# SCH_SD_CARD_2024-02-26.net
KiCad netlist of a schematic drawn in EasyEDA
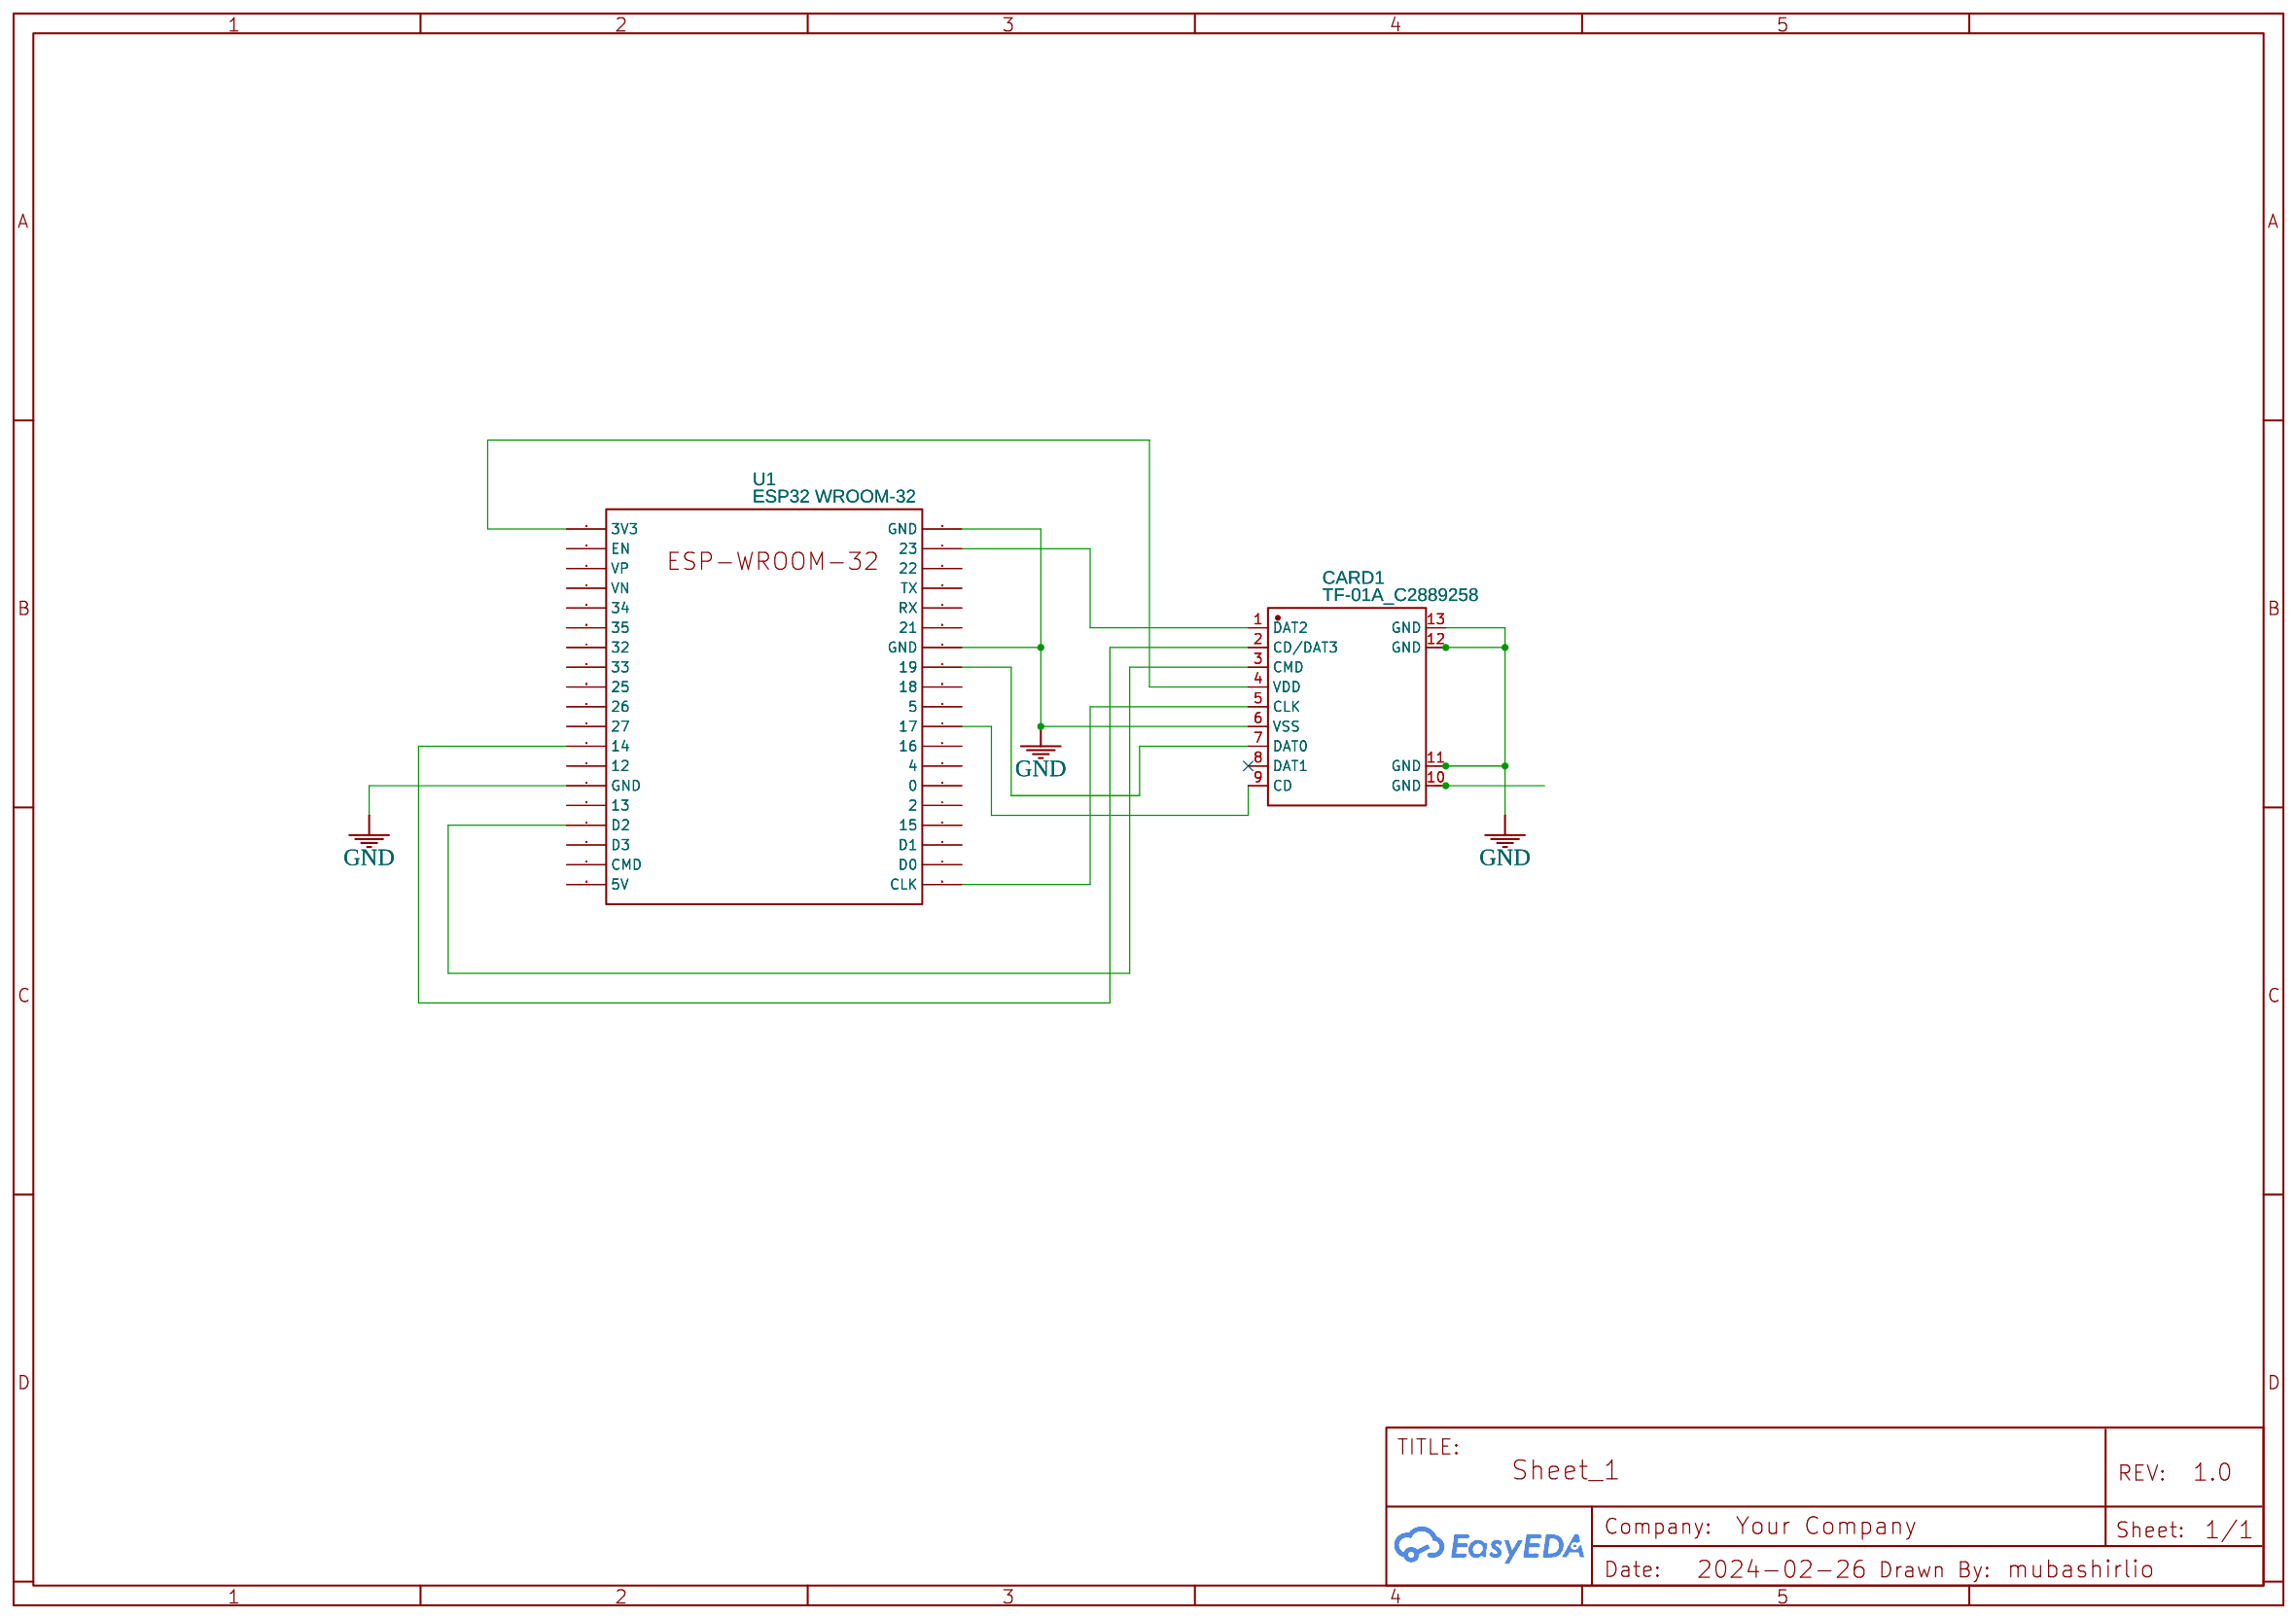
[diagram p0: schematic sheet]

(export (version "E")
  (design (tool "Eeschema 10.0.6"))
  (components
    (comp (ref "CARD1")
      (value "TF-01A_C2889258")
      (fields (field (name "Manufacturer Part") "TF-01A") (field (name "Manufacturer") "Yuandi(台湾元迪)"))
      (libsource (lib "") (part "TF-01A_C2889258"))
    )
    (comp (ref "U1") (value "ESP32 WROOM-32") (libsource (lib "") (part "ESP32 WROOM-32")))
  )
  (nets
    (net (code "1") (name "GND") (class "Default")
      (node (ref "CARD1") (pin "11") (pinfunction "GND_11") (pintype "unspecified"))
      (node (ref "CARD1") (pin "12") (pinfunction "GND_12") (pintype "unspecified"))
      (node (ref "CARD1") (pin "13") (pinfunction "GND_13") (pintype "unspecified"))
      (node (ref "CARD1") (pin "6") (pinfunction "VSS_6") (pintype "unspecified"))
      (node (ref "U1") (pin "14") (pinfunction "GND_14") (pintype "unspecified"))
      (node (ref "U1") (pin "32") (pinfunction "GND_32") (pintype "unspecified"))
      (node (ref "U1") (pin "38") (pinfunction "GND_38") (pintype "unspecified"))
    )
    (net (code "2") (name "Net-(CARD1-CD)") (class "Default")
      (node (ref "CARD1") (pin "9") (pinfunction "CD_9") (pintype "unspecified"))
      (node (ref "U1") (pin "28") (pinfunction "17_28") (pintype "unspecified"))
    )
    (net (code "3") (name "Net-(CARD1-CD{slash}DAT3)") (class "Default")
      (node (ref "CARD1") (pin "2") (pinfunction "CD/DAT3_2") (pintype "unspecified"))
      (node (ref "U1") (pin "12") (pinfunction "14_12") (pintype "unspecified"))
    )
    (net (code "4") (name "Net-(CARD1-CLK)") (class "Default")
      (node (ref "CARD1") (pin "5") (pinfunction "CLK_5") (pintype "unspecified"))
      (node (ref "U1") (pin "20") (pinfunction "CLK_20") (pintype "unspecified"))
    )
    (net (code "5") (name "Net-(CARD1-CMD)") (class "Default")
      (node (ref "CARD1") (pin "3") (pinfunction "CMD_3") (pintype "unspecified"))
      (node (ref "U1") (pin "16") (pinfunction "D2_16") (pintype "unspecified"))
    )
    (net (code "6") (name "Net-(CARD1-DAT0)") (class "Default")
      (node (ref "CARD1") (pin "7") (pinfunction "DAT0_7") (pintype "unspecified"))
      (node (ref "U1") (pin "31") (pinfunction "19_31") (pintype "unspecified"))
    )
    (net (code "7") (name "Net-(CARD1-DAT2)") (class "Default")
      (node (ref "CARD1") (pin "1") (pinfunction "DAT2_1") (pintype "unspecified"))
      (node (ref "U1") (pin "37") (pinfunction "23_37") (pintype "unspecified"))
    )
    (net (code "8") (name "Net-(CARD1-VDD)") (class "Default")
      (node (ref "CARD1") (pin "4") (pinfunction "VDD_4") (pintype "unspecified"))
      (node (ref "U1") (pin "1") (pinfunction "3V3_1") (pintype "unspecified"))
    )
    (net (code "9") (name "unconnected-(CARD1-DAT1-Pad8)") (class "Default")
      (node (ref "CARD1") (pin "8") (pinfunction "DAT1_8") (pintype "unspecified+no_connect"))
    )
    (net (code "10") (name "unconnected-(CARD1-GND-Pad10)") (class "Default")
      (node (ref "CARD1") (pin "10") (pinfunction "GND_10") (pintype "unspecified"))
    )
    (net (code "11") (name "unconnected-(U1-0-Pad25)") (class "Default")
      (node (ref "U1") (pin "25") (pinfunction "0_25") (pintype "unspecified"))
    )
    (net (code "12") (name "unconnected-(U1-2-Pad24)") (class "Default")
      (node (ref "U1") (pin "24") (pinfunction "2_24") (pintype "unspecified"))
    )
    (net (code "13") (name "unconnected-(U1-4-Pad26)") (class "Default")
      (node (ref "U1") (pin "26") (pinfunction "4_26") (pintype "unspecified"))
    )
    (net (code "14") (name "unconnected-(U1-5-Pad29)") (class "Default")
      (node (ref "U1") (pin "29") (pinfunction "5_29") (pintype "unspecified"))
    )
    (net (code "15") (name "unconnected-(U1-5V-Pad19)") (class "Default")
      (node (ref "U1") (pin "19") (pinfunction "5V_19") (pintype "unspecified"))
    )
    (net (code "16") (name "unconnected-(U1-12-Pad13)") (class "Default")
      (node (ref "U1") (pin "13") (pinfunction "12_13") (pintype "unspecified"))
    )
    (net (code "17") (name "unconnected-(U1-13-Pad15)") (class "Default")
      (node (ref "U1") (pin "15") (pinfunction "13_15") (pintype "unspecified"))
    )
    (net (code "18") (name "unconnected-(U1-15-Pad23)") (class "Default")
      (node (ref "U1") (pin "23") (pinfunction "15_23") (pintype "unspecified"))
    )
    (net (code "19") (name "unconnected-(U1-16-Pad27)") (class "Default")
      (node (ref "U1") (pin "27") (pinfunction "16_27") (pintype "unspecified"))
    )
    (net (code "20") (name "unconnected-(U1-18-Pad30)") (class "Default")
      (node (ref "U1") (pin "30") (pinfunction "18_30") (pintype "unspecified"))
    )
    (net (code "21") (name "unconnected-(U1-21-Pad33)") (class "Default")
      (node (ref "U1") (pin "33") (pinfunction "21_33") (pintype "unspecified"))
    )
    (net (code "22") (name "unconnected-(U1-22-Pad36)") (class "Default")
      (node (ref "U1") (pin "36") (pinfunction "22_36") (pintype "unspecified"))
    )
    (net (code "23") (name "unconnected-(U1-25-Pad9)") (class "Default")
      (node (ref "U1") (pin "9") (pinfunction "25_9") (pintype "unspecified"))
    )
    (net (code "24") (name "unconnected-(U1-26-Pad10)") (class "Default")
      (node (ref "U1") (pin "10") (pinfunction "26_10") (pintype "unspecified"))
    )
    (net (code "25") (name "unconnected-(U1-27-Pad11)") (class "Default")
      (node (ref "U1") (pin "11") (pinfunction "27_11") (pintype "unspecified"))
    )
    (net (code "26") (name "unconnected-(U1-32-Pad7)") (class "Default")
      (node (ref "U1") (pin "7") (pinfunction "32_7") (pintype "unspecified"))
    )
    (net (code "27") (name "unconnected-(U1-33-Pad8)") (class "Default")
      (node (ref "U1") (pin "8") (pinfunction "33_8") (pintype "unspecified"))
    )
    (net (code "28") (name "unconnected-(U1-34-Pad5)") (class "Default")
      (node (ref "U1") (pin "5") (pinfunction "34_5") (pintype "unspecified"))
    )
    (net (code "29") (name "unconnected-(U1-35-Pad6)") (class "Default")
      (node (ref "U1") (pin "6") (pinfunction "35_6") (pintype "unspecified"))
    )
    (net (code "30") (name "unconnected-(U1-CMD-Pad18)") (class "Default")
      (node (ref "U1") (pin "18") (pinfunction "CMD_18") (pintype "unspecified"))
    )
    (net (code "31") (name "unconnected-(U1-D0-Pad21)") (class "Default")
      (node (ref "U1") (pin "21") (pinfunction "D0_21") (pintype "unspecified"))
    )
    (net (code "32") (name "unconnected-(U1-D1-Pad22)") (class "Default")
      (node (ref "U1") (pin "22") (pinfunction "D1_22") (pintype "unspecified"))
    )
    (net (code "33") (name "unconnected-(U1-D3-Pad17)") (class "Default")
      (node (ref "U1") (pin "17") (pinfunction "D3_17") (pintype "unspecified"))
    )
    (net (code "34") (name "unconnected-(U1-EN-Pad2)") (class "Default")
      (node (ref "U1") (pin "2") (pinfunction "EN_2") (pintype "unspecified"))
    )
    (net (code "35") (name "unconnected-(U1-RX-Pad34)") (class "Default")
      (node (ref "U1") (pin "34") (pinfunction "RX_34") (pintype "unspecified"))
    )
    (net (code "36") (name "unconnected-(U1-TX-Pad35)") (class "Default")
      (node (ref "U1") (pin "35") (pinfunction "TX_35") (pintype "unspecified"))
    )
    (net (code "37") (name "unconnected-(U1-VN-Pad4)") (class "Default")
      (node (ref "U1") (pin "4") (pinfunction "VN_4") (pintype "unspecified"))
    )
    (net (code "38") (name "unconnected-(U1-VP-Pad3)") (class "Default")
      (node (ref "U1") (pin "3") (pinfunction "VP_3") (pintype "unspecified"))
    )
  )
)
